# Control_Board_V2.net
KiCad netlist of a schematic drawn in EAGLE
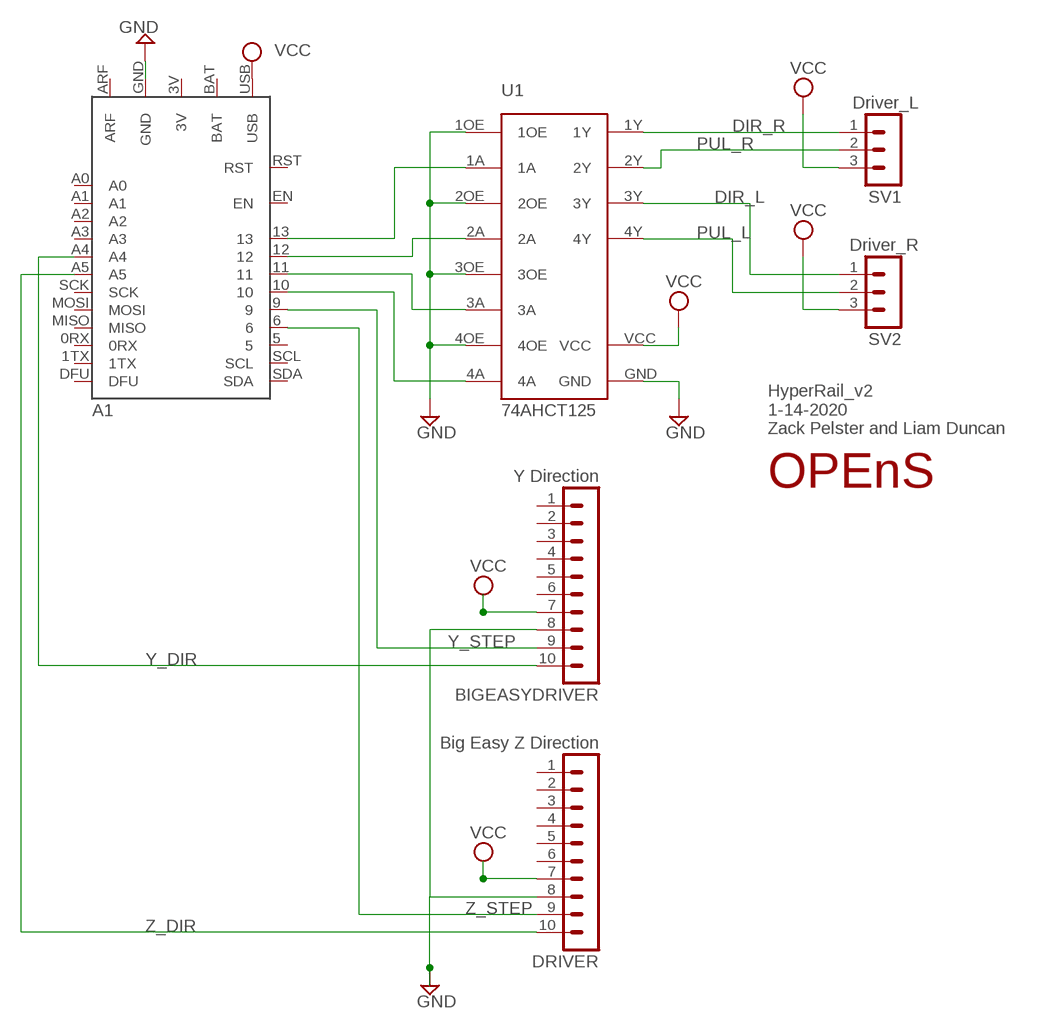
[diagram p0: schematic, sheet 1]

(export (version "E")
  (design (tool "Eeschema 10.0.6"))
  (components
    (comp (ref "A1")
      (value "FEATHER_BLUEFRUIT_M0")
      (footprint "eagle-import:FEATHER_BLUEFRUIT_M0")
      (libsource (lib "eagle-import") (part "FEATHER_BLUEFRUIT_M0"))
    )
    (comp (ref "BIGEASYDRIVER")
      (value "Y Direction")
      (footprint "eagle-import:MA10-1")
      (libsource (lib "eagle-import") (part "MA10-1"))
    )
    (comp (ref "DRIVER")
      (value "Big Easy Z Direction")
      (footprint "eagle-import:MA10-1")
      (libsource (lib "eagle-import") (part "MA10-1"))
    )
    (comp (ref "SV1")
      (value "Driver_L")
      (footprint "eagle-import:MA03-1")
      (libsource (lib "eagle-import") (part "MA03-1"))
    )
    (comp (ref "SV2")
      (value "Driver_R")
      (footprint "eagle-import:MA03-1")
      (libsource (lib "eagle-import") (part "MA03-1"))
    )
    (comp (ref "U$1")
      (value "OPENS-LOGO")
      (footprint "eagle-import:OPENS-LOGO")
      (libsource (lib "eagle-import") (part "OPENS-LOGO"))
    )
    (comp (ref "U1")
      (value "74AHCT125")
      (footprint "eagle-import:74AHCT125")
      (libsource (lib "eagle-import") (part "74AHCT125"))
    )
  )
  (nets
    (net (code "1") (name "/3V") (class "Default")
      (node (ref "A1") (pin "3V") (pinfunction "3V_3V") (pintype "power_in"))
    )
    (net (code "2") (name "/BAT") (class "Default")
      (node (ref "A1") (pin "BAT") (pinfunction "BAT_BAT") (pintype "power_in"))
    )
    (net (code "3") (name "/DIR_L") (class "Default")
      (node (ref "SV2") (pin "1") (pinfunction "1_1") (pintype "passive"))
      (node (ref "U1") (pin "3Y") (pinfunction "3Y_3Y") (pintype "bidirectional"))
    )
    (net (code "4") (name "/DIR_R") (class "Default")
      (node (ref "SV1") (pin "1") (pinfunction "1_1") (pintype "passive"))
      (node (ref "U1") (pin "1Y") (pinfunction "1Y_1Y") (pintype "bidirectional"))
    )
    (net (code "5") (name "/PUL_L") (class "Default")
      (node (ref "SV2") (pin "2") (pinfunction "2_2") (pintype "passive"))
      (node (ref "U1") (pin "4Y") (pinfunction "4Y_4Y") (pintype "bidirectional"))
    )
    (net (code "6") (name "/PUL_R") (class "Default")
      (node (ref "SV1") (pin "2") (pinfunction "2_2") (pintype "passive"))
      (node (ref "U1") (pin "2Y") (pinfunction "2Y_2Y") (pintype "bidirectional"))
    )
    (net (code "7") (name "/Y_DIR") (class "Default")
      (node (ref "A1") (pin "A4") (pinfunction "A4_A4") (pintype "bidirectional"))
      (node (ref "BIGEASYDRIVER") (pin "10") (pinfunction "10_10") (pintype "passive"))
    )
    (net (code "8") (name "/Y_STEP") (class "Default")
      (node (ref "A1") (pin "9") (pinfunction "9_9") (pintype "bidirectional"))
      (node (ref "BIGEASYDRIVER") (pin "9") (pinfunction "9_9") (pintype "passive"))
    )
    (net (code "9") (name "/Z_DIR") (class "Default")
      (node (ref "A1") (pin "A5") (pinfunction "A5_A5") (pintype "bidirectional"))
      (node (ref "DRIVER") (pin "10") (pinfunction "10_10") (pintype "passive"))
    )
    (net (code "10") (name "/Z_STEP") (class "Default")
      (node (ref "A1") (pin "6") (pinfunction "6_6") (pintype "bidirectional"))
      (node (ref "DRIVER") (pin "9") (pinfunction "9_9") (pintype "passive"))
    )
    (net (code "11") (name "GND") (class "Default")
      (node (ref "A1") (pin "GND") (pinfunction "GND_GND") (pintype "power_in"))
      (node (ref "BIGEASYDRIVER") (pin "8") (pinfunction "8_8") (pintype "passive"))
      (node (ref "DRIVER") (pin "8") (pinfunction "8_8") (pintype "passive"))
      (node (ref "U1") (pin "1OE") (pinfunction "1OE_1OE") (pintype "bidirectional"))
      (node (ref "U1") (pin "2OE") (pinfunction "2OE_2OE") (pintype "bidirectional"))
      (node (ref "U1") (pin "3OE") (pinfunction "3OE_3OE") (pintype "bidirectional"))
      (node (ref "U1") (pin "4OE") (pinfunction "4OE_4OE") (pintype "bidirectional"))
      (node (ref "U1") (pin "GND") (pinfunction "GND_GND") (pintype "bidirectional"))
    )
    (net (code "12") (name "Net-(A1-Pad10)") (class "Default")
      (node (ref "A1") (pin "10") (pinfunction "10_10") (pintype "bidirectional"))
      (node (ref "U1") (pin "4A") (pinfunction "4A_4A") (pintype "bidirectional"))
    )
    (net (code "13") (name "Net-(A1-Pad11)") (class "Default")
      (node (ref "A1") (pin "11") (pinfunction "11_11") (pintype "bidirectional"))
      (node (ref "U1") (pin "3A") (pinfunction "3A_3A") (pintype "bidirectional"))
    )
    (net (code "14") (name "Net-(A1-Pad12)") (class "Default")
      (node (ref "A1") (pin "12") (pinfunction "12_12") (pintype "bidirectional"))
      (node (ref "U1") (pin "2A") (pinfunction "2A_2A") (pintype "bidirectional"))
    )
    (net (code "15") (name "Net-(A1-Pad13)") (class "Default")
      (node (ref "A1") (pin "13") (pinfunction "13_13") (pintype "bidirectional"))
      (node (ref "U1") (pin "1A") (pinfunction "1A_1A") (pintype "bidirectional"))
    )
    (net (code "16") (name "VCC") (class "Default")
      (node (ref "A1") (pin "USB") (pinfunction "USB_USB") (pintype "power_in"))
      (node (ref "BIGEASYDRIVER") (pin "7") (pinfunction "7_7") (pintype "passive"))
      (node (ref "DRIVER") (pin "7") (pinfunction "7_7") (pintype "passive"))
      (node (ref "SV1") (pin "3") (pinfunction "3_3") (pintype "passive"))
      (node (ref "SV2") (pin "3") (pinfunction "3_3") (pintype "passive"))
      (node (ref "U1") (pin "VCC") (pinfunction "VCC_VCC") (pintype "bidirectional"))
    )
    (net (code "17") (name "unconnected-(A1-Pad0RX)") (class "Default")
      (node (ref "A1") (pin "0RX") (pinfunction "0RX_0RX") (pintype "bidirectional"))
    )
    (net (code "18") (name "unconnected-(A1-Pad1TX)") (class "Default")
      (node (ref "A1") (pin "1TX") (pinfunction "1TX_1TX") (pintype "bidirectional"))
    )
    (net (code "19") (name "unconnected-(A1-Pad5)") (class "Default")
      (node (ref "A1") (pin "5") (pinfunction "5_5") (pintype "bidirectional"))
    )
    (net (code "20") (name "unconnected-(A1-PadA0)") (class "Default")
      (node (ref "A1") (pin "A0") (pinfunction "A0_A0") (pintype "bidirectional"))
    )
    (net (code "21") (name "unconnected-(A1-PadA1)") (class "Default")
      (node (ref "A1") (pin "A1") (pinfunction "A1_A1") (pintype "bidirectional"))
    )
    (net (code "22") (name "unconnected-(A1-PadA2)") (class "Default")
      (node (ref "A1") (pin "A2") (pinfunction "A2_A2") (pintype "bidirectional"))
    )
    (net (code "23") (name "unconnected-(A1-PadA3)") (class "Default")
      (node (ref "A1") (pin "A3") (pinfunction "A3_A3") (pintype "bidirectional"))
    )
    (net (code "24") (name "unconnected-(A1-PadARF)") (class "Default")
      (node (ref "A1") (pin "ARF") (pinfunction "ARF_ARF") (pintype "bidirectional"))
    )
    (net (code "25") (name "unconnected-(A1-PadDFU)") (class "Default")
      (node (ref "A1") (pin "DFU") (pinfunction "DFU_DFU") (pintype "bidirectional"))
    )
    (net (code "26") (name "unconnected-(A1-PadEN)") (class "Default")
      (node (ref "A1") (pin "EN") (pinfunction "EN_EN") (pintype "bidirectional"))
    )
    (net (code "27") (name "unconnected-(A1-PadMISO)") (class "Default")
      (node (ref "A1") (pin "MISO") (pinfunction "MISO_MISO") (pintype "bidirectional"))
    )
    (net (code "28") (name "unconnected-(A1-PadMOSI)") (class "Default")
      (node (ref "A1") (pin "MOSI") (pinfunction "MOSI_MOSI") (pintype "bidirectional"))
    )
    (net (code "29") (name "unconnected-(A1-PadRST)") (class "Default")
      (node (ref "A1") (pin "RST") (pinfunction "RST_RST") (pintype "bidirectional"))
    )
    (net (code "30") (name "unconnected-(A1-PadSCK)") (class "Default")
      (node (ref "A1") (pin "SCK") (pinfunction "SCK_SCK") (pintype "bidirectional"))
    )
    (net (code "31") (name "unconnected-(A1-PadSCL)") (class "Default")
      (node (ref "A1") (pin "SCL") (pinfunction "SCL_SCL") (pintype "bidirectional"))
    )
    (net (code "32") (name "unconnected-(A1-PadSDA)") (class "Default")
      (node (ref "A1") (pin "SDA") (pinfunction "SDA_SDA") (pintype "bidirectional"))
    )
    (net (code "33") (name "unconnected-(BIGEASYDRIVER-Pad1)") (class "Default")
      (node (ref "BIGEASYDRIVER") (pin "1") (pinfunction "1_1") (pintype "passive"))
    )
    (net (code "34") (name "unconnected-(BIGEASYDRIVER-Pad2)") (class "Default")
      (node (ref "BIGEASYDRIVER") (pin "2") (pinfunction "2_2") (pintype "passive"))
    )
    (net (code "35") (name "unconnected-(BIGEASYDRIVER-Pad3)") (class "Default")
      (node (ref "BIGEASYDRIVER") (pin "3") (pinfunction "3_3") (pintype "passive"))
    )
    (net (code "36") (name "unconnected-(BIGEASYDRIVER-Pad4)") (class "Default")
      (node (ref "BIGEASYDRIVER") (pin "4") (pinfunction "4_4") (pintype "passive"))
    )
    (net (code "37") (name "unconnected-(BIGEASYDRIVER-Pad5)") (class "Default")
      (node (ref "BIGEASYDRIVER") (pin "5") (pinfunction "5_5") (pintype "passive"))
    )
    (net (code "38") (name "unconnected-(BIGEASYDRIVER-Pad6)") (class "Default")
      (node (ref "BIGEASYDRIVER") (pin "6") (pinfunction "6_6") (pintype "passive"))
    )
    (net (code "39") (name "unconnected-(DRIVER-Pad1)") (class "Default")
      (node (ref "DRIVER") (pin "1") (pinfunction "1_1") (pintype "passive"))
    )
    (net (code "40") (name "unconnected-(DRIVER-Pad2)") (class "Default")
      (node (ref "DRIVER") (pin "2") (pinfunction "2_2") (pintype "passive"))
    )
    (net (code "41") (name "unconnected-(DRIVER-Pad3)") (class "Default")
      (node (ref "DRIVER") (pin "3") (pinfunction "3_3") (pintype "passive"))
    )
    (net (code "42") (name "unconnected-(DRIVER-Pad4)") (class "Default")
      (node (ref "DRIVER") (pin "4") (pinfunction "4_4") (pintype "passive"))
    )
    (net (code "43") (name "unconnected-(DRIVER-Pad5)") (class "Default")
      (node (ref "DRIVER") (pin "5") (pinfunction "5_5") (pintype "passive"))
    )
    (net (code "44") (name "unconnected-(DRIVER-Pad6)") (class "Default")
      (node (ref "DRIVER") (pin "6") (pinfunction "6_6") (pintype "passive"))
    )
  )
)
